# MicroSD.net
KiCad netlist of a schematic drawn in Altium Designer
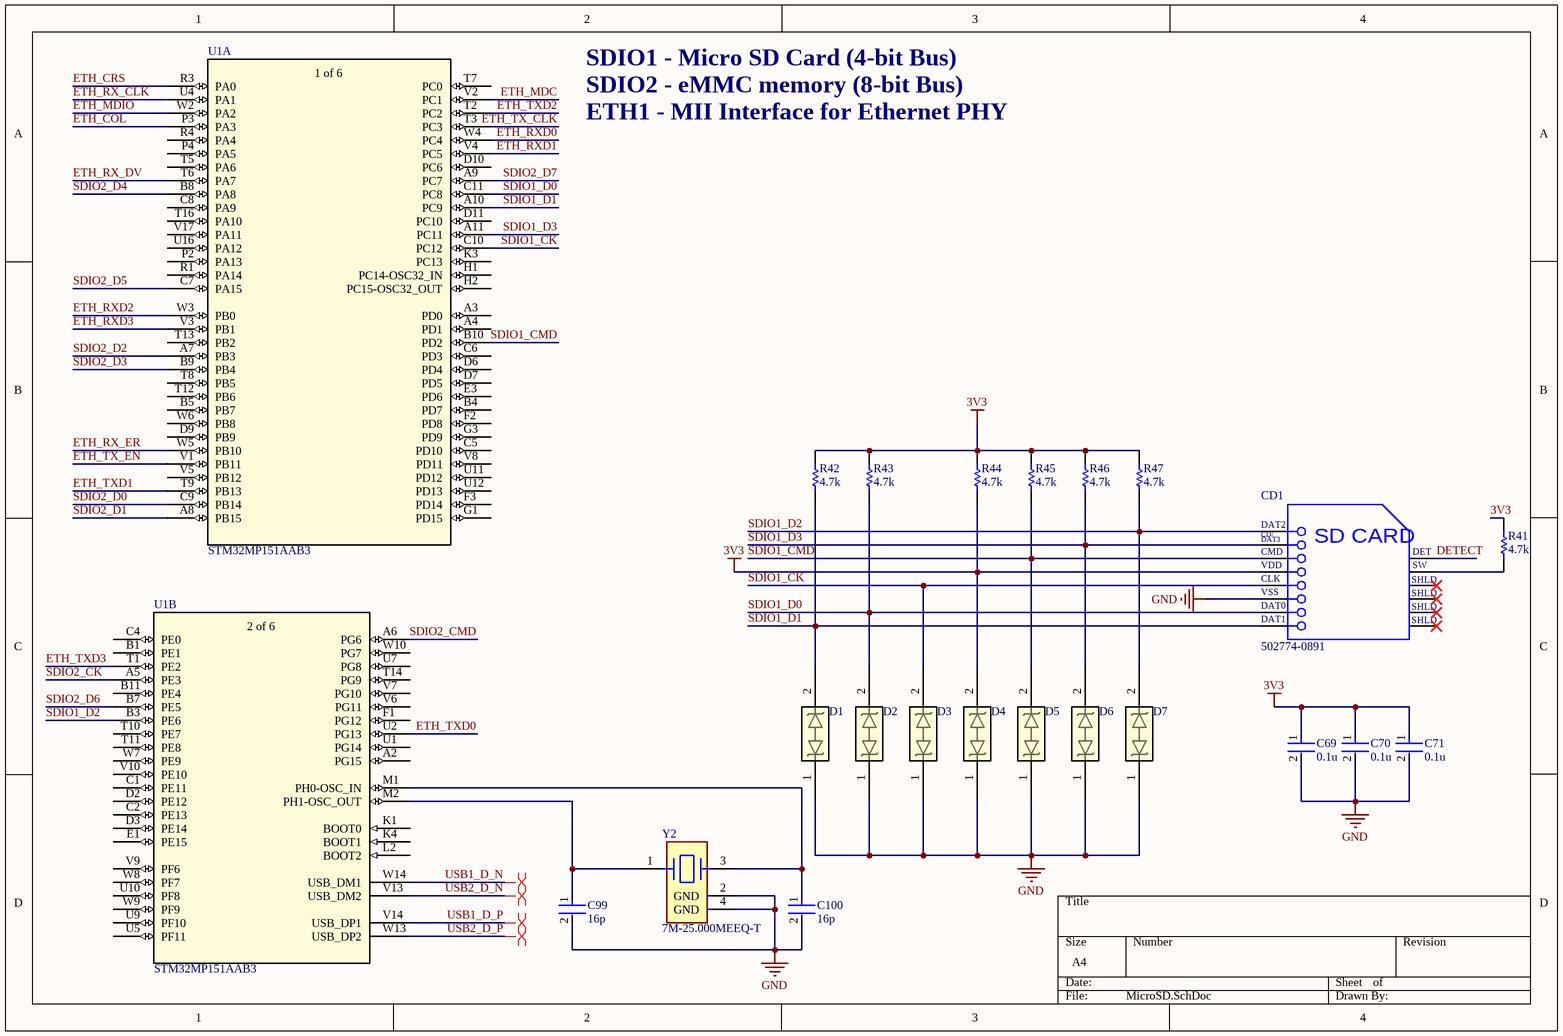
[diagram p0: MicroSD.SchDoc]

(export (version "E")
  (design (tool "Eeschema 10.0.6"))
  (components
    (comp (ref "C69")
      (value "0.1u")
      (footprint "FP-C0603C-CF-MFG")
      (description "CAP CER 0.1UF 50V X7R 0603")
      (fields (field (name "TOLERANCE") "0.1") (field (name "MANUFACTURER") "KEMET"))
      (libsource (lib "Altium Content Vault") (part "b4654b650e69147ec39a6b967a45e02"))
    )
    (comp (ref "C70")
      (value "0.1u")
      (footprint "FP-C0603C-CF-MFG")
      (description "CAP CER 0.1UF 50V X7R 0603")
      (fields (field (name "TOLERANCE") "0.1") (field (name "MANUFACTURER") "KEMET"))
      (libsource (lib "Altium Content Vault") (part "b4654b650e69147ec39a6b967a45e02"))
    )
    (comp (ref "C71")
      (value "0.1u")
      (footprint "FP-C0603C-CF-MFG")
      (description "CAP CER 0.1UF 50V X7R 0603")
      (fields (field (name "TOLERANCE") "0.1") (field (name "MANUFACTURER") "KEMET"))
      (libsource (lib "Altium Content Vault") (part "b4654b650e69147ec39a6b967a45e02"))
    )
    (comp (ref "C99")
      (value "16p")
      (footprint "FP-C0603C-CF-MFG")
      (description "CAP CER 0.1UF 50V X7R 0603")
      (fields (field (name "TOLERANCE") "0.1") (field (name "MANUFACTURER") "KEMET"))
      (libsource (lib "Altium Content Vault") (part "b4654b650e69147ec39a6b967a45e02"))
    )
    (comp (ref "C100")
      (value "16p")
      (footprint "FP-C0603C-CF-MFG")
      (description "CAP CER 0.1UF 50V X7R 0603")
      (fields (field (name "TOLERANCE") "0.1") (field (name "MANUFACTURER") "KEMET"))
      (libsource (lib "Altium Content Vault") (part "b4654b650e69147ec39a6b967a45e02"))
    )
    (comp (ref "CD1")
      (value "502774-0891")
      (footprint "MOLX-502774-0891_V")
      (description "Micro SD Memory Card Connector, 0.5 A, 10 V (DC), -25 to 85 degC, 8-Pin SMT, RoHS, Tape and Reel")
      (fields (field (name "MANUFACTURER") "Molex"))
      (libsource (lib "Altium Content Vault") (part "CN-SD-8-2SW-4S_B"))
    )
    (comp (ref "D1")
      (value "DESD5V0U1BA-7")
      (footprint "SOD-323")
      (description "No Description Available")
      (fields (field (name "COPYRIGHT") "Copyright (C) 2023 Ultra Librarian. All rights reserved."))
      (libsource (lib "DESD5V0U1BA-7") (part "DESD5V0U1BA-7"))
    )
    (comp (ref "D2")
      (value "DESD5V0U1BA-7")
      (footprint "SOD-323")
      (description "No Description Available")
      (fields (field (name "COPYRIGHT") "Copyright (C) 2023 Ultra Librarian. All rights reserved."))
      (libsource (lib "DESD5V0U1BA-7") (part "DESD5V0U1BA-7"))
    )
    (comp (ref "D3")
      (value "DESD5V0U1BA-7")
      (footprint "SOD-323")
      (description "No Description Available")
      (fields (field (name "COPYRIGHT") "Copyright (C) 2023 Ultra Librarian. All rights reserved."))
      (libsource (lib "DESD5V0U1BA-7") (part "DESD5V0U1BA-7"))
    )
    (comp (ref "D4")
      (value "DESD5V0U1BA-7")
      (footprint "SOD-323")
      (description "No Description Available")
      (fields (field (name "COPYRIGHT") "Copyright (C) 2023 Ultra Librarian. All rights reserved."))
      (libsource (lib "DESD5V0U1BA-7") (part "DESD5V0U1BA-7"))
    )
    (comp (ref "D5")
      (value "DESD5V0U1BA-7")
      (footprint "SOD-323")
      (description "No Description Available")
      (fields (field (name "COPYRIGHT") "Copyright (C) 2023 Ultra Librarian. All rights reserved."))
      (libsource (lib "DESD5V0U1BA-7") (part "DESD5V0U1BA-7"))
    )
    (comp (ref "D6")
      (value "DESD5V0U1BA-7")
      (footprint "SOD-323")
      (description "No Description Available")
      (fields (field (name "COPYRIGHT") "Copyright (C) 2023 Ultra Librarian. All rights reserved."))
      (libsource (lib "DESD5V0U1BA-7") (part "DESD5V0U1BA-7"))
    )
    (comp (ref "D7")
      (value "DESD5V0U1BA-7")
      (footprint "SOD-323")
      (description "No Description Available")
      (fields (field (name "COPYRIGHT") "Copyright (C) 2023 Ultra Librarian. All rights reserved."))
      (libsource (lib "DESD5V0U1BA-7") (part "DESD5V0U1BA-7"))
    )
    (comp (ref "R41")
      (value "4.7k")
      (footprint "RESC1609X50X30NL8T20")
      (description "Chip Resistor, 10 KOhm, +/- 1%, 100 mW, -55 to 155 degC, 0603 (1608 Metric), RoHS, Tape and Reel")
      (fields (field (name "MANUFACTURER") "Vishay Semiconductor"))
      (libsource (lib "Altium Content Vault") (part "RES-2"))
    )
    (comp (ref "R42")
      (value "4.7k")
      (footprint "RESC1609X50X30NL8T20")
      (description "Chip Resistor, 10 KOhm, +/- 1%, 100 mW, -55 to 155 degC, 0603 (1608 Metric), RoHS, Tape and Reel")
      (fields (field (name "MANUFACTURER") "Vishay Semiconductor"))
      (libsource (lib "Altium Content Vault") (part "RES-2"))
    )
    (comp (ref "R43")
      (value "4.7k")
      (footprint "RESC1609X50X30NL8T20")
      (description "Chip Resistor, 10 KOhm, +/- 1%, 100 mW, -55 to 155 degC, 0603 (1608 Metric), RoHS, Tape and Reel")
      (fields (field (name "MANUFACTURER") "Vishay Semiconductor"))
      (libsource (lib "Altium Content Vault") (part "RES-2"))
    )
    (comp (ref "R44")
      (value "4.7k")
      (footprint "RESC1609X50X30NL8T20")
      (description "Chip Resistor, 10 KOhm, +/- 1%, 100 mW, -55 to 155 degC, 0603 (1608 Metric), RoHS, Tape and Reel")
      (fields (field (name "MANUFACTURER") "Vishay Semiconductor"))
      (libsource (lib "Altium Content Vault") (part "RES-2"))
    )
    (comp (ref "R45")
      (value "4.7k")
      (footprint "RESC1609X50X30NL8T20")
      (description "Chip Resistor, 10 KOhm, +/- 1%, 100 mW, -55 to 155 degC, 0603 (1608 Metric), RoHS, Tape and Reel")
      (fields (field (name "MANUFACTURER") "Vishay Semiconductor"))
      (libsource (lib "Altium Content Vault") (part "RES-2"))
    )
    (comp (ref "R46")
      (value "4.7k")
      (footprint "RESC1609X50X30NL8T20")
      (description "Chip Resistor, 10 KOhm, +/- 1%, 100 mW, -55 to 155 degC, 0603 (1608 Metric), RoHS, Tape and Reel")
      (fields (field (name "MANUFACTURER") "Vishay Semiconductor"))
      (libsource (lib "Altium Content Vault") (part "RES-2"))
    )
    (comp (ref "R47")
      (value "4.7k")
      (footprint "RESC1609X50X30NL8T20")
      (description "Chip Resistor, 10 KOhm, +/- 1%, 100 mW, -55 to 155 degC, 0603 (1608 Metric), RoHS, Tape and Reel")
      (fields (field (name "MANUFACTURER") "Vishay Semiconductor"))
      (libsource (lib "Altium Content Vault") (part "RES-2"))
    )
    (comp (ref "U1")
      (value "STM32MP151AAB3")
      (footprint "LFBGA354_16X16_STM")
      (description "No Description Available")
      (libsource (lib "Master") (part "STM32MP151AAB3"))
    )
    (comp (ref "Y2")
      (value "7M-25.000MEEQ-T")
      (footprint "FP-7M-MFG")
      (description "Crystal 25MHz, 10ppm, 10pF, 50Ω")
      (fields (field (name "TOLERANCE") "10ppm"))
      (libsource (lib "Altium Content Vault") (part "41079aabb0e87794b56622915be14ed"))
    )
  )
  (nets
    (net (code "1") (name "/DETECT") (class "Default")
      (node (ref "CD1") (pin "9") (pinfunction "DETECT_9") (pintype "passive"))
    )
    (net (code "2") (name "/ETH_COL") (class "Default")
      (node (ref "U1") (pin "P3") (pinfunction "PA3_P3") (pintype "bidirectional"))
    )
    (net (code "3") (name "/ETH_CRS") (class "Default")
      (node (ref "U1") (pin "R3") (pinfunction "PA0_R3") (pintype "bidirectional"))
    )
    (net (code "4") (name "/ETH_MDC") (class "Default")
      (node (ref "U1") (pin "V2") (pinfunction "PC1_V2") (pintype "bidirectional"))
    )
    (net (code "5") (name "/ETH_MDIO") (class "Default")
      (node (ref "U1") (pin "W2") (pinfunction "PA2_W2") (pintype "bidirectional"))
    )
    (net (code "6") (name "/ETH_RXD0") (class "Default")
      (node (ref "U1") (pin "W4") (pinfunction "PC4_W4") (pintype "bidirectional"))
    )
    (net (code "7") (name "/ETH_RXD1") (class "Default")
      (node (ref "U1") (pin "V4") (pinfunction "PC5_V4") (pintype "bidirectional"))
    )
    (net (code "8") (name "/ETH_RXD2") (class "Default")
      (node (ref "U1") (pin "W3") (pinfunction "PB0_W3") (pintype "bidirectional"))
    )
    (net (code "9") (name "/ETH_RXD3") (class "Default")
      (node (ref "U1") (pin "V3") (pinfunction "PB1_V3") (pintype "bidirectional"))
    )
    (net (code "10") (name "/ETH_RX_CLK") (class "Default")
      (node (ref "U1") (pin "U4") (pinfunction "PA1_U4") (pintype "bidirectional"))
    )
    (net (code "11") (name "/ETH_RX_DV") (class "Default")
      (node (ref "U1") (pin "T6") (pinfunction "PA7_T6") (pintype "bidirectional"))
    )
    (net (code "12") (name "/ETH_RX_ER") (class "Default")
      (node (ref "U1") (pin "W5") (pinfunction "PB10_W5") (pintype "bidirectional"))
    )
    (net (code "13") (name "/ETH_TXD0") (class "Default")
      (node (ref "U1") (pin "U2") (pinfunction "PG13_U2") (pintype "bidirectional"))
    )
    (net (code "14") (name "/ETH_TXD1") (class "Default")
      (node (ref "U1") (pin "T9") (pinfunction "PB13_T9") (pintype "bidirectional"))
    )
    (net (code "15") (name "/ETH_TXD2") (class "Default")
      (node (ref "U1") (pin "T2") (pinfunction "PC2_T2") (pintype "bidirectional"))
    )
    (net (code "16") (name "/ETH_TXD3") (class "Default")
      (node (ref "U1") (pin "T1") (pinfunction "PE2_T1") (pintype "bidirectional"))
    )
    (net (code "17") (name "/ETH_TX_CLK") (class "Default")
      (node (ref "U1") (pin "T3") (pinfunction "PC3_T3") (pintype "bidirectional"))
    )
    (net (code "18") (name "/ETH_TX_EN") (class "Default")
      (node (ref "U1") (pin "V1") (pinfunction "PB11_V1") (pintype "bidirectional"))
    )
    (net (code "19") (name "/SDIO1_CK") (class "Default")
      (node (ref "CD1") (pin "5") (pinfunction "CLK_5") (pintype "passive"))
      (node (ref "D3") (pin "2") (pinfunction "2_2") (pintype "passive"))
      (node (ref "U1") (pin "C10") (pinfunction "PC12_C10") (pintype "bidirectional"))
    )
    (net (code "20") (name "/SDIO1_CMD") (class "Default")
      (node (ref "CD1") (pin "3") (pinfunction "CMD_3") (pintype "passive"))
      (node (ref "D5") (pin "2") (pinfunction "2_2") (pintype "passive"))
      (node (ref "R45") (pin "1") (pinfunction "1_1") (pintype "passive"))
      (node (ref "U1") (pin "B10") (pinfunction "PD2_B10") (pintype "bidirectional"))
    )
    (net (code "21") (name "/SDIO1_D0") (class "Default")
      (node (ref "CD1") (pin "7") (pinfunction "DAT0_7") (pintype "passive"))
      (node (ref "D2") (pin "2") (pinfunction "2_2") (pintype "passive"))
      (node (ref "R43") (pin "1") (pinfunction "1_1") (pintype "passive"))
      (node (ref "U1") (pin "C11") (pinfunction "PC8_C11") (pintype "bidirectional"))
    )
    (net (code "22") (name "/SDIO1_D1") (class "Default")
      (node (ref "CD1") (pin "8") (pinfunction "DAT1_8") (pintype "passive"))
      (node (ref "D1") (pin "2") (pinfunction "2_2") (pintype "passive"))
      (node (ref "R42") (pin "1") (pinfunction "1_1") (pintype "passive"))
      (node (ref "U1") (pin "A10") (pinfunction "PC9_A10") (pintype "bidirectional"))
    )
    (net (code "23") (name "/SDIO1_D2") (class "Default")
      (node (ref "CD1") (pin "1") (pinfunction "DAT2_1") (pintype "passive"))
      (node (ref "D7") (pin "2") (pinfunction "2_2") (pintype "passive"))
      (node (ref "R47") (pin "1") (pinfunction "1_1") (pintype "passive"))
      (node (ref "U1") (pin "B3") (pinfunction "PE6_B3") (pintype "bidirectional"))
    )
    (net (code "24") (name "/SDIO1_D3") (class "Default")
      (node (ref "CD1") (pin "2") (pinfunction "CD/DAT3_2") (pintype "passive"))
      (node (ref "D6") (pin "2") (pinfunction "2_2") (pintype "passive"))
      (node (ref "R46") (pin "1") (pinfunction "1_1") (pintype "passive"))
      (node (ref "U1") (pin "A11") (pinfunction "PC11_A11") (pintype "bidirectional"))
    )
    (net (code "25") (name "/SDIO2_CK") (class "Default")
      (node (ref "U1") (pin "A5") (pinfunction "PE3_A5") (pintype "bidirectional"))
    )
    (net (code "26") (name "/SDIO2_CMD") (class "Default")
      (node (ref "U1") (pin "A6") (pinfunction "PG6_A6") (pintype "bidirectional"))
    )
    (net (code "27") (name "/SDIO2_D0") (class "Default")
      (node (ref "U1") (pin "C9") (pinfunction "PB14_C9") (pintype "bidirectional"))
    )
    (net (code "28") (name "/SDIO2_D1") (class "Default")
      (node (ref "U1") (pin "A8") (pinfunction "PB15_A8") (pintype "bidirectional"))
    )
    (net (code "29") (name "/SDIO2_D2") (class "Default")
      (node (ref "U1") (pin "A7") (pinfunction "PB3_A7") (pintype "bidirectional"))
    )
    (net (code "30") (name "/SDIO2_D3") (class "Default")
      (node (ref "U1") (pin "B9") (pinfunction "PB4_B9") (pintype "bidirectional"))
    )
    (net (code "31") (name "/SDIO2_D4") (class "Default")
      (node (ref "U1") (pin "B8") (pinfunction "PA8_B8") (pintype "bidirectional"))
    )
    (net (code "32") (name "/SDIO2_D5") (class "Default")
      (node (ref "U1") (pin "C7") (pinfunction "PA15_C7") (pintype "bidirectional"))
    )
    (net (code "33") (name "/SDIO2_D6") (class "Default")
      (node (ref "U1") (pin "B7") (pinfunction "PE5_B7") (pintype "bidirectional"))
    )
    (net (code "34") (name "/SDIO2_D7") (class "Default")
      (node (ref "U1") (pin "A9") (pinfunction "PC7_A9") (pintype "bidirectional"))
    )
    (net (code "35") (name "/USB1_D_N") (class "Default")
      (node (ref "U1") (pin "W14") (pinfunction "USB_DM1_W14") (pintype "passive"))
    )
    (net (code "36") (name "/USB1_D_P") (class "Default")
      (node (ref "U1") (pin "V14") (pinfunction "USB_DP1_V14") (pintype "passive"))
    )
    (net (code "37") (name "/USB2_D_N") (class "Default")
      (node (ref "U1") (pin "V13") (pinfunction "USB_DM2_V13") (pintype "passive"))
    )
    (net (code "38") (name "/USB2_D_P") (class "Default")
      (node (ref "U1") (pin "W13") (pinfunction "USB_DP2_W13") (pintype "passive"))
    )
    (net (code "39") (name "3V3") (class "Default")
      (node (ref "C69") (pin "1") (pinfunction "1_1") (pintype "passive"))
      (node (ref "C70") (pin "1") (pinfunction "1_1") (pintype "passive"))
      (node (ref "C71") (pin "1") (pinfunction "1_1") (pintype "passive"))
      (node (ref "CD1") (pin "4") (pinfunction "VDD_4") (pintype "passive"))
      (node (ref "D4") (pin "2") (pinfunction "2_2") (pintype "passive"))
      (node (ref "R41") (pin "2") (pinfunction "2_2") (pintype "passive"))
      (node (ref "R42") (pin "2") (pinfunction "2_2") (pintype "passive"))
      (node (ref "R43") (pin "2") (pinfunction "2_2") (pintype "passive"))
      (node (ref "R44") (pin "1") (pinfunction "1_1") (pintype "passive"))
      (node (ref "R44") (pin "2") (pinfunction "2_2") (pintype "passive"))
      (node (ref "R45") (pin "2") (pinfunction "2_2") (pintype "passive"))
      (node (ref "R46") (pin "2") (pinfunction "2_2") (pintype "passive"))
      (node (ref "R47") (pin "2") (pinfunction "2_2") (pintype "passive"))
    )
    (net (code "40") (name "GND") (class "Default")
      (node (ref "C100") (pin "2") (pinfunction "2_2") (pintype "passive"))
      (node (ref "C69") (pin "2") (pinfunction "2_2") (pintype "passive"))
      (node (ref "C70") (pin "2") (pinfunction "2_2") (pintype "passive"))
      (node (ref "C71") (pin "2") (pinfunction "2_2") (pintype "passive"))
      (node (ref "C99") (pin "2") (pinfunction "2_2") (pintype "passive"))
      (node (ref "CD1") (pin "6") (pinfunction "VSS_6") (pintype "passive"))
      (node (ref "D1") (pin "1") (pinfunction "1_1") (pintype "passive"))
      (node (ref "D2") (pin "1") (pinfunction "1_1") (pintype "passive"))
      (node (ref "D3") (pin "1") (pinfunction "1_1") (pintype "passive"))
      (node (ref "D4") (pin "1") (pinfunction "1_1") (pintype "passive"))
      (node (ref "D5") (pin "1") (pinfunction "1_1") (pintype "passive"))
      (node (ref "D6") (pin "1") (pinfunction "1_1") (pintype "passive"))
      (node (ref "D7") (pin "1") (pinfunction "1_1") (pintype "passive"))
      (node (ref "Y2") (pin "2") (pinfunction "GND_2") (pintype "power_in"))
      (node (ref "Y2") (pin "4") (pinfunction "GND_4") (pintype "power_in"))
    )
    (net (code "41") (name "Net-(CD1-SWITCH)") (class "Default")
      (node (ref "CD1") (pin "10") (pinfunction "SWITCH_10") (pintype "passive"))
      (node (ref "R41") (pin "1") (pinfunction "1_1") (pintype "passive"))
    )
    (net (code "42") (name "Net-(U1B-PH0-OSC_IN)") (class "Default")
      (node (ref "C100") (pin "1") (pinfunction "1_1") (pintype "passive"))
      (node (ref "U1") (pin "M1") (pinfunction "PH0-OSC_IN_M1") (pintype "bidirectional"))
      (node (ref "Y2") (pin "3") (pinfunction "3_3") (pintype "passive"))
    )
    (net (code "43") (name "Net-(U1B-PH1-OSC_OUT)") (class "Default")
      (node (ref "C99") (pin "1") (pinfunction "1_1") (pintype "passive"))
      (node (ref "U1") (pin "M2") (pinfunction "PH1-OSC_OUT_M2") (pintype "bidirectional"))
      (node (ref "Y2") (pin "1") (pinfunction "1_1") (pintype "passive"))
    )
    (net (code "44") (name "unconnected-(CD1-SHLD-Pad11)") (class "Default")
      (node (ref "CD1") (pin "11") (pinfunction "SHLD_11") (pintype "passive+no_connect"))
    )
    (net (code "45") (name "unconnected-(CD1-SHLD-Pad12)") (class "Default")
      (node (ref "CD1") (pin "12") (pinfunction "SHLD_12") (pintype "passive+no_connect"))
    )
    (net (code "46") (name "unconnected-(CD1-SHLD-Pad13)") (class "Default")
      (node (ref "CD1") (pin "13") (pinfunction "SHLD_13") (pintype "passive+no_connect"))
    )
    (net (code "47") (name "unconnected-(CD1-SHLD-Pad14)") (class "Default")
      (node (ref "CD1") (pin "14") (pinfunction "SHLD_14") (pintype "passive+no_connect"))
    )
    (net (code "48") (name "unconnected-(U1A-PA4-PadR4)") (class "Default")
      (node (ref "U1") (pin "R4") (pinfunction "PA4_R4") (pintype "bidirectional"))
    )
    (net (code "49") (name "unconnected-(U1A-PA5-PadP4)") (class "Default")
      (node (ref "U1") (pin "P4") (pinfunction "PA5_P4") (pintype "bidirectional"))
    )
    (net (code "50") (name "unconnected-(U1A-PA6-PadT5)") (class "Default")
      (node (ref "U1") (pin "T5") (pinfunction "PA6_T5") (pintype "bidirectional"))
    )
    (net (code "51") (name "unconnected-(U1A-PA9-PadC8)") (class "Default")
      (node (ref "U1") (pin "C8") (pinfunction "PA9_C8") (pintype "bidirectional"))
    )
    (net (code "52") (name "unconnected-(U1A-PA10-PadT16)") (class "Default")
      (node (ref "U1") (pin "T16") (pinfunction "PA10_T16") (pintype "bidirectional"))
    )
    (net (code "53") (name "unconnected-(U1A-PA11-PadV17)") (class "Default")
      (node (ref "U1") (pin "V17") (pinfunction "PA11_V17") (pintype "bidirectional"))
    )
    (net (code "54") (name "unconnected-(U1A-PA12-PadU16)") (class "Default")
      (node (ref "U1") (pin "U16") (pinfunction "PA12_U16") (pintype "bidirectional"))
    )
    (net (code "55") (name "unconnected-(U1A-PA13-PadP2)") (class "Default")
      (node (ref "U1") (pin "P2") (pinfunction "PA13_P2") (pintype "bidirectional"))
    )
    (net (code "56") (name "unconnected-(U1A-PA14-PadR1)") (class "Default")
      (node (ref "U1") (pin "R1") (pinfunction "PA14_R1") (pintype "bidirectional"))
    )
    (net (code "57") (name "unconnected-(U1A-PB2-PadT13)") (class "Default")
      (node (ref "U1") (pin "T13") (pinfunction "PB2_T13") (pintype "bidirectional"))
    )
    (net (code "58") (name "unconnected-(U1A-PB5-PadT8)") (class "Default")
      (node (ref "U1") (pin "T8") (pinfunction "PB5_T8") (pintype "bidirectional"))
    )
    (net (code "59") (name "unconnected-(U1A-PB6-PadT12)") (class "Default")
      (node (ref "U1") (pin "T12") (pinfunction "PB6_T12") (pintype "bidirectional"))
    )
    (net (code "60") (name "unconnected-(U1A-PB7-PadB5)") (class "Default")
      (node (ref "U1") (pin "B5") (pinfunction "PB7_B5") (pintype "bidirectional"))
    )
    (net (code "61") (name "unconnected-(U1A-PB8-PadW6)") (class "Default")
      (node (ref "U1") (pin "W6") (pinfunction "PB8_W6") (pintype "bidirectional"))
    )
    (net (code "62") (name "unconnected-(U1A-PB9-PadD9)") (class "Default")
      (node (ref "U1") (pin "D9") (pinfunction "PB9_D9") (pintype "bidirectional"))
    )
    (net (code "63") (name "unconnected-(U1A-PB12-PadV5)") (class "Default")
      (node (ref "U1") (pin "V5") (pinfunction "PB12_V5") (pintype "bidirectional"))
    )
    (net (code "64") (name "unconnected-(U1A-PC0-PadT7)") (class "Default")
      (node (ref "U1") (pin "T7") (pinfunction "PC0_T7") (pintype "bidirectional"))
    )
    (net (code "65") (name "unconnected-(U1A-PC6-PadD10)") (class "Default")
      (node (ref "U1") (pin "D10") (pinfunction "PC6_D10") (pintype "bidirectional"))
    )
    (net (code "66") (name "unconnected-(U1A-PC10-PadD11)") (class "Default")
      (node (ref "U1") (pin "D11") (pinfunction "PC10_D11") (pintype "bidirectional"))
    )
    (net (code "67") (name "unconnected-(U1A-PC13-PadK3)") (class "Default")
      (node (ref "U1") (pin "K3") (pinfunction "PC13_K3") (pintype "bidirectional"))
    )
    (net (code "68") (name "unconnected-(U1A-PC14-OSC32_IN-PadH1)") (class "Default")
      (node (ref "U1") (pin "H1") (pinfunction "PC14-OSC32_IN_H1") (pintype "bidirectional"))
    )
    (net (code "69") (name "unconnected-(U1A-PC15-OSC32_OUT-PadH2)") (class "Default")
      (node (ref "U1") (pin "H2") (pinfunction "PC15-OSC32_OUT_H2") (pintype "bidirectional"))
    )
    (net (code "70") (name "unconnected-(U1A-PD0-PadA3)") (class "Default")
      (node (ref "U1") (pin "A3") (pinfunction "PD0_A3") (pintype "bidirectional"))
    )
    (net (code "71") (name "unconnected-(U1A-PD1-PadA4)") (class "Default")
      (node (ref "U1") (pin "A4") (pinfunction "PD1_A4") (pintype "bidirectional"))
    )
    (net (code "72") (name "unconnected-(U1A-PD3-PadC6)") (class "Default")
      (node (ref "U1") (pin "C6") (pinfunction "PD3_C6") (pintype "bidirectional"))
    )
    (net (code "73") (name "unconnected-(U1A-PD4-PadD6)") (class "Default")
      (node (ref "U1") (pin "D6") (pinfunction "PD4_D6") (pintype "bidirectional"))
    )
    (net (code "74") (name "unconnected-(U1A-PD5-PadD7)") (class "Default")
      (node (ref "U1") (pin "D7") (pinfunction "PD5_D7") (pintype "bidirectional"))
    )
    (net (code "75") (name "unconnected-(U1A-PD6-PadE3)") (class "Default")
      (node (ref "U1") (pin "E3") (pinfunction "PD6_E3") (pintype "bidirectional"))
    )
    (net (code "76") (name "unconnected-(U1A-PD7-PadB4)") (class "Default")
      (node (ref "U1") (pin "B4") (pinfunction "PD7_B4") (pintype "bidirectional"))
    )
    (net (code "77") (name "unconnected-(U1A-PD8-PadF2)") (class "Default")
      (node (ref "U1") (pin "F2") (pinfunction "PD8_F2") (pintype "bidirectional"))
    )
    (net (code "78") (name "unconnected-(U1A-PD9-PadG3)") (class "Default")
      (node (ref "U1") (pin "G3") (pinfunction "PD9_G3") (pintype "bidirectional"))
    )
    (net (code "79") (name "unconnected-(U1A-PD10-PadC5)") (class "Default")
      (node (ref "U1") (pin "C5") (pinfunction "PD10_C5") (pintype "bidirectional"))
    )
    (net (code "80") (name "unconnected-(U1A-PD11-PadV8)") (class "Default")
      (node (ref "U1") (pin "V8") (pinfunction "PD11_V8") (pintype "bidirectional"))
    )
    (net (code "81") (name "unconnected-(U1A-PD12-PadU11)") (class "Default")
      (node (ref "U1") (pin "U11") (pinfunction "PD12_U11") (pintype "bidirectional"))
    )
    (net (code "82") (name "unconnected-(U1A-PD13-PadU12)") (class "Default")
      (node (ref "U1") (pin "U12") (pinfunction "PD13_U12") (pintype "bidirectional"))
    )
    (net (code "83") (name "unconnected-(U1A-PD14-PadF3)") (class "Default")
      (node (ref "U1") (pin "F3") (pinfunction "PD14_F3") (pintype "bidirectional"))
    )
    (net (code "84") (name "unconnected-(U1A-PD15-PadG1)") (class "Default")
      (node (ref "U1") (pin "G1") (pinfunction "PD15_G1") (pintype "bidirectional"))
    )
    (net (code "85") (name "unconnected-(U1B-BOOT0-PadK1)") (class "Default")
      (node (ref "U1") (pin "K1") (pinfunction "BOOT0_K1") (pintype "input"))
    )
    (net (code "86") (name "unconnected-(U1B-BOOT1-PadK4)") (class "Default")
      (node (ref "U1") (pin "K4") (pinfunction "BOOT1_K4") (pintype "input"))
    )
    (net (code "87") (name "unconnected-(U1B-BOOT2-PadL2)") (class "Default")
      (node (ref "U1") (pin "L2") (pinfunction "BOOT2_L2") (pintype "input"))
    )
    (net (code "88") (name "unconnected-(U1B-PE0-PadC4)") (class "Default")
      (node (ref "U1") (pin "C4") (pinfunction "PE0_C4") (pintype "bidirectional"))
    )
    (net (code "89") (name "unconnected-(U1B-PE1-PadB1)") (class "Default")
      (node (ref "U1") (pin "B1") (pinfunction "PE1_B1") (pintype "bidirectional"))
    )
    (net (code "90") (name "unconnected-(U1B-PE4-PadB11)") (class "Default")
      (node (ref "U1") (pin "B11") (pinfunction "PE4_B11") (pintype "bidirectional"))
    )
    (net (code "91") (name "unconnected-(U1B-PE7-PadT10)") (class "Default")
      (node (ref "U1") (pin "T10") (pinfunction "PE7_T10") (pintype "bidirectional"))
    )
    (net (code "92") (name "unconnected-(U1B-PE8-PadT11)") (class "Default")
      (node (ref "U1") (pin "T11") (pinfunction "PE8_T11") (pintype "bidirectional"))
    )
    (net (code "93") (name "unconnected-(U1B-PE9-PadW7)") (class "Default")
      (node (ref "U1") (pin "W7") (pinfunction "PE9_W7") (pintype "bidirectional"))
    )
    (net (code "94") (name "unconnected-(U1B-PE10-PadV10)") (class "Default")
      (node (ref "U1") (pin "V10") (pinfunction "PE10_V10") (pintype "bidirectional"))
    )
    (net (code "95") (name "unconnected-(U1B-PE11-PadC1)") (class "Default")
      (node (ref "U1") (pin "C1") (pinfunction "PE11_C1") (pintype "bidirectional"))
    )
    (net (code "96") (name "unconnected-(U1B-PE12-PadD2)") (class "Default")
      (node (ref "U1") (pin "D2") (pinfunction "PE12_D2") (pintype "bidirectional"))
    )
    (net (code "97") (name "unconnected-(U1B-PE13-PadC2)") (class "Default")
      (node (ref "U1") (pin "C2") (pinfunction "PE13_C2") (pintype "bidirectional"))
    )
    (net (code "98") (name "unconnected-(U1B-PE14-PadD3)") (class "Default")
      (node (ref "U1") (pin "D3") (pinfunction "PE14_D3") (pintype "bidirectional"))
    )
    (net (code "99") (name "unconnected-(U1B-PE15-PadE1)") (class "Default")
      (node (ref "U1") (pin "E1") (pinfunction "PE15_E1") (pintype "bidirectional"))
    )
    (net (code "100") (name "unconnected-(U1B-PF6-PadV9)") (class "Default")
      (node (ref "U1") (pin "V9") (pinfunction "PF6_V9") (pintype "bidirectional"))
    )
    (net (code "101") (name "unconnected-(U1B-PF7-PadW8)") (class "Default")
      (node (ref "U1") (pin "W8") (pinfunction "PF7_W8") (pintype "bidirectional"))
    )
    (net (code "102") (name "unconnected-(U1B-PF8-PadU10)") (class "Default")
      (node (ref "U1") (pin "U10") (pinfunction "PF8_U10") (pintype "bidirectional"))
    )
    (net (code "103") (name "unconnected-(U1B-PF9-PadW9)") (class "Default")
      (node (ref "U1") (pin "W9") (pinfunction "PF9_W9") (pintype "bidirectional"))
    )
    (net (code "104") (name "unconnected-(U1B-PF10-PadU9)") (class "Default")
      (node (ref "U1") (pin "U9") (pinfunction "PF10_U9") (pintype "bidirectional"))
    )
    (net (code "105") (name "unconnected-(U1B-PF11-PadU5)") (class "Default")
      (node (ref "U1") (pin "U5") (pinfunction "PF11_U5") (pintype "bidirectional"))
    )
    (net (code "106") (name "unconnected-(U1B-PG7-PadW10)") (class "Default")
      (node (ref "U1") (pin "W10") (pinfunction "PG7_W10") (pintype "bidirectional"))
    )
    (net (code "107") (name "unconnected-(U1B-PG8-PadU7)") (class "Default")
      (node (ref "U1") (pin "U7") (pinfunction "PG8_U7") (pintype "bidirectional"))
    )
    (net (code "108") (name "unconnected-(U1B-PG9-PadT14)") (class "Default")
      (node (ref "U1") (pin "T14") (pinfunction "PG9_T14") (pintype "bidirectional"))
    )
    (net (code "109") (name "unconnected-(U1B-PG10-PadV7)") (class "Default")
      (node (ref "U1") (pin "V7") (pinfunction "PG10_V7") (pintype "bidirectional"))
    )
    (net (code "110") (name "unconnected-(U1B-PG11-PadV6)") (class "Default")
      (node (ref "U1") (pin "V6") (pinfunction "PG11_V6") (pintype "bidirectional"))
    )
    (net (code "111") (name "unconnected-(U1B-PG12-PadF1)") (class "Default")
      (node (ref "U1") (pin "F1") (pinfunction "PG12_F1") (pintype "bidirectional"))
    )
    (net (code "112") (name "unconnected-(U1B-PG14-PadU1)") (class "Default")
      (node (ref "U1") (pin "U1") (pinfunction "PG14_U1") (pintype "bidirectional"))
    )
    (net (code "113") (name "unconnected-(U1B-PG15-PadA2)") (class "Default")
      (node (ref "U1") (pin "A2") (pinfunction "PG15_A2") (pintype "bidirectional"))
    )
  )
)
